# SCH.net
KiCad netlist of a schematic drawn in EasyEDA
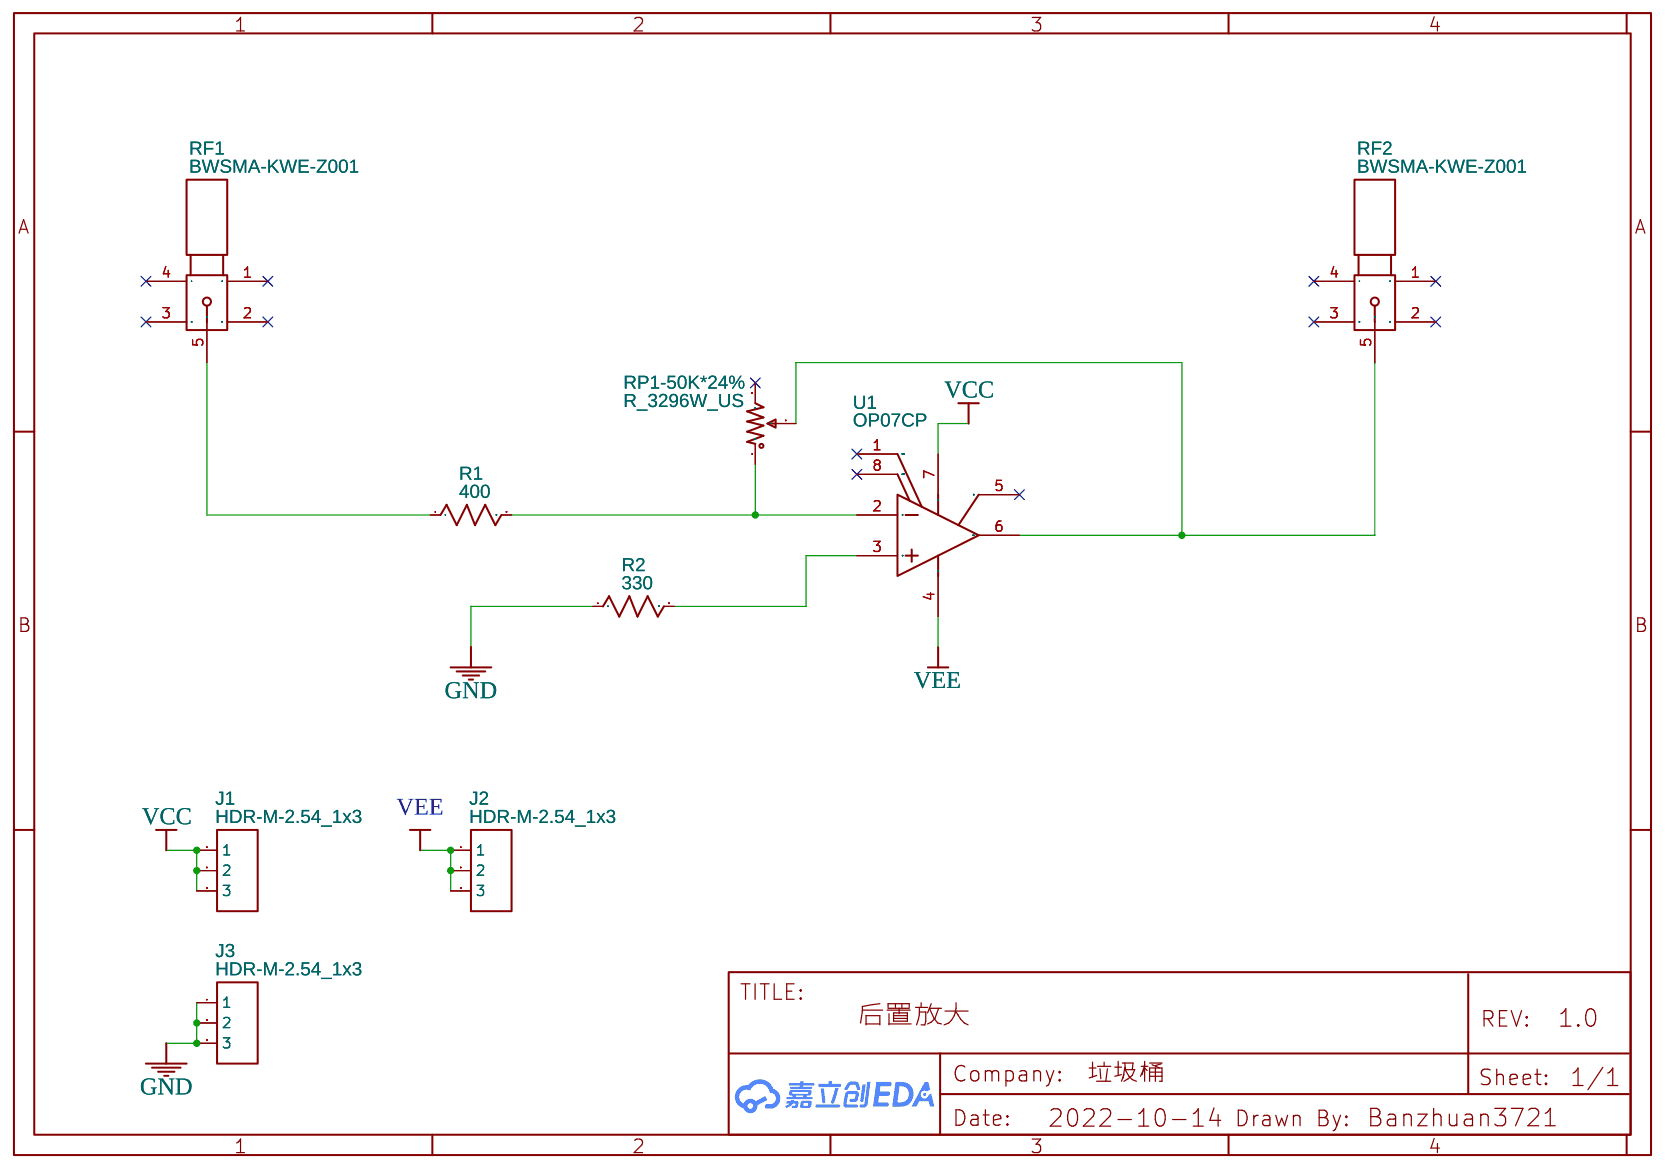
[diagram p0: schematic sheet]

(export (version "E")
  (design (tool "Eeschema 10.0.6"))
  (components
    (comp (ref "J1")
      (value "HDR-M-2.54_1x3")
      (fields (field (name "BOM_Supplier Part") "C180248"))
      (libsource (lib "") (part "HDR-M-2.54_1x3"))
    )
    (comp (ref "J2")
      (value "HDR-M-2.54_1x3")
      (fields (field (name "BOM_Supplier Part") "C180248"))
      (libsource (lib "") (part "HDR-M-2.54_1x3"))
    )
    (comp (ref "J3")
      (value "HDR-M-2.54_1x3")
      (fields (field (name "BOM_Supplier Part") "C180248"))
      (libsource (lib "") (part "HDR-M-2.54_1x3"))
    )
    (comp (ref "R1") (value "400") (libsource (lib "") (part "R_AXIAL-0.3_US")))
    (comp (ref "R2") (value "330") (libsource (lib "") (part "R_AXIAL-0.3_US")))
    (comp (ref "RF1")
      (value "BWSMA-KWE-Z001")
      (fields (field (name "BOM_Supplier Part") "C496551"))
      (libsource (lib "") (part "BWSMA-KWE-Z001"))
    )
    (comp (ref "RF2")
      (value "BWSMA-KWE-Z001")
      (fields (field (name "BOM_Supplier Part") "C496551"))
      (libsource (lib "") (part "BWSMA-KWE-Z001"))
    )
    (comp (ref "RP1-50K*24%") (value "R_3296W_US") (libsource (lib "") (part "R_3296W_US")))
    (comp (ref "U1")
      (value "OP07CP")
      (fields (field (name "BOM_Supplier Part") "C5224"))
      (libsource (lib "") (part "OP07CP"))
    )
  )
  (nets
    (net (code "1") (name "GND") (class "Default")
      (node (ref "J3") (pin "1") (pinfunction "1_1") (pintype "input"))
      (node (ref "J3") (pin "2") (pinfunction "2_2") (pintype "input"))
      (node (ref "J3") (pin "3") (pinfunction "3_3") (pintype "input"))
      (node (ref "R2") (pin "1") (pinfunction "1_1") (pintype "unspecified"))
    )
    (net (code "2") (name "Net-(R1-Pad1)") (class "Default")
      (node (ref "R1") (pin "1") (pinfunction "1_1") (pintype "unspecified"))
      (node (ref "RF1") (pin "5") (pinfunction "5_5") (pintype "unspecified"))
    )
    (net (code "3") (name "Net-(U1-IN+)") (class "Default")
      (node (ref "R2") (pin "2") (pinfunction "2_2") (pintype "unspecified"))
      (node (ref "U1") (pin "3") (pinfunction "IN+_3") (pintype "unspecified"))
    )
    (net (code "4") (name "Net-(U1-IN-)") (class "Default")
      (node (ref "R1") (pin "2") (pinfunction "2_2") (pintype "unspecified"))
      (node (ref "RP1-50K*24%") (pin "1") (pinfunction "1_1") (pintype "unspecified"))
      (node (ref "U1") (pin "2") (pinfunction "IN-_2") (pintype "unspecified"))
    )
    (net (code "5") (name "Net-(U1-OUT)") (class "Default")
      (node (ref "RF2") (pin "5") (pinfunction "5_5") (pintype "unspecified"))
      (node (ref "RP1-50K*24%") (pin "2") (pinfunction "2_2") (pintype "unspecified"))
      (node (ref "U1") (pin "6") (pinfunction "OUT_6") (pintype "output"))
    )
    (net (code "6") (name "VCC") (class "Default")
      (node (ref "J1") (pin "1") (pinfunction "1_1") (pintype "input"))
      (node (ref "J1") (pin "2") (pinfunction "2_2") (pintype "input"))
      (node (ref "J1") (pin "3") (pinfunction "3_3") (pintype "input"))
      (node (ref "U1") (pin "7") (pinfunction "VCC+_7") (pintype "passive"))
    )
    (net (code "7") (name "VEE") (class "Default")
      (node (ref "J2") (pin "1") (pinfunction "1_1") (pintype "input"))
      (node (ref "J2") (pin "2") (pinfunction "2_2") (pintype "input"))
      (node (ref "J2") (pin "3") (pinfunction "3_3") (pintype "input"))
      (node (ref "U1") (pin "4") (pinfunction "VCC-_4") (pintype "passive"))
    )
    (net (code "8") (name "unconnected-(RF1-Pad1)") (class "Default")
      (node (ref "RF1") (pin "1") (pinfunction "1_1") (pintype "unspecified+no_connect"))
    )
    (net (code "9") (name "unconnected-(RF1-Pad2)") (class "Default")
      (node (ref "RF1") (pin "2") (pinfunction "2_2") (pintype "unspecified+no_connect"))
    )
    (net (code "10") (name "unconnected-(RF1-Pad3)") (class "Default")
      (node (ref "RF1") (pin "3") (pinfunction "3_3") (pintype "unspecified+no_connect"))
    )
    (net (code "11") (name "unconnected-(RF1-Pad4)") (class "Default")
      (node (ref "RF1") (pin "4") (pinfunction "4_4") (pintype "unspecified+no_connect"))
    )
    (net (code "12") (name "unconnected-(RF2-Pad1)") (class "Default")
      (node (ref "RF2") (pin "1") (pinfunction "1_1") (pintype "unspecified+no_connect"))
    )
    (net (code "13") (name "unconnected-(RF2-Pad2)") (class "Default")
      (node (ref "RF2") (pin "2") (pinfunction "2_2") (pintype "unspecified+no_connect"))
    )
    (net (code "14") (name "unconnected-(RF2-Pad3)") (class "Default")
      (node (ref "RF2") (pin "3") (pinfunction "3_3") (pintype "unspecified+no_connect"))
    )
    (net (code "15") (name "unconnected-(RF2-Pad4)") (class "Default")
      (node (ref "RF2") (pin "4") (pinfunction "4_4") (pintype "unspecified+no_connect"))
    )
    (net (code "16") (name "unconnected-(RP1-50K*24%-Pad3)") (class "Default")
      (node (ref "RP1-50K*24%") (pin "3") (pinfunction "3_3") (pintype "unspecified+no_connect"))
    )
    (net (code "17") (name "unconnected-(U1-NC-Pad5)") (class "Default")
      (node (ref "U1") (pin "5") (pinfunction "NC_5") (pintype "unspecified+no_connect"))
    )
    (net (code "18") (name "unconnected-(U1-OFFSET_N1-Pad1)") (class "Default")
      (node (ref "U1") (pin "1") (pinfunction "OFFSET_N1_1") (pintype "unspecified+no_connect"))
    )
    (net (code "19") (name "unconnected-(U1-OFFSET_N2-Pad8)") (class "Default")
      (node (ref "U1") (pin "8") (pinfunction "OFFSET_N2_8") (pintype "unspecified+no_connect"))
    )
  )
)
